# Main_Board_-_Single_v20_v4.net
KiCad netlist of a schematic drawn in EAGLE
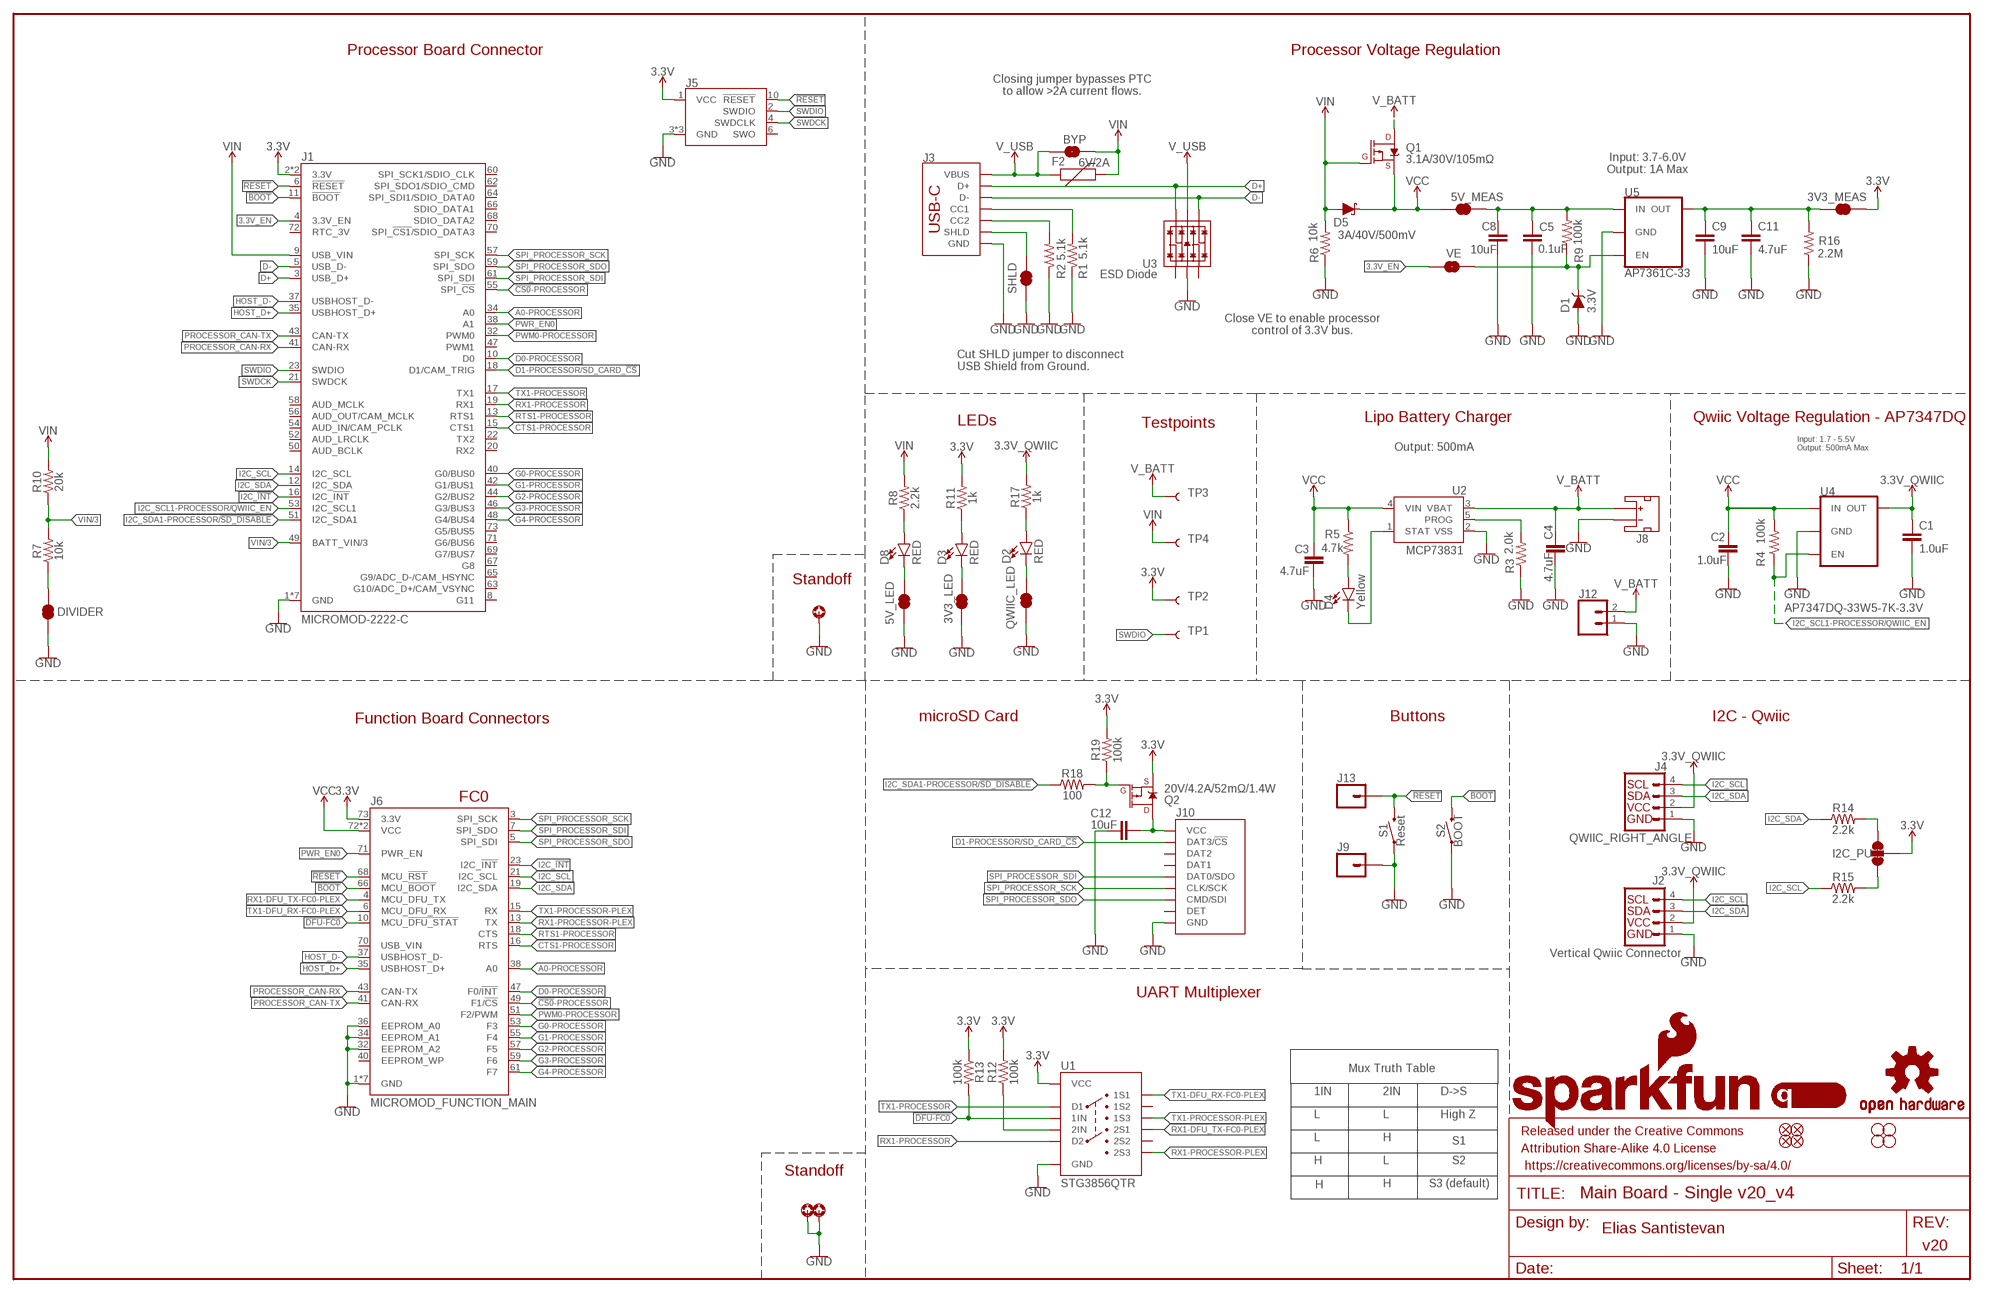
[diagram p0: schematic, sheet 1]

(export (version "E")
  (design (tool "Eeschema 10.0.6"))
  (components
    (comp (ref "3V3_LED")
      (value "JUMPER-SMT_2_NC_TRACE_SILK")
      (footprint "eagle-import:SMT-JUMPER_2_NC_TRACE_SILK")
      (libsource (lib "eagle-import") (part "JUMPER-SMT_2_NC_TRACE_SILK"))
    )
    (comp (ref "3V3_MEAS")
      (value "JUMPER-COMBO_2_NC_TRACE")
      (footprint "eagle-import:COMBO-JUMPER_2_NC_TRACE")
      (libsource (lib "eagle-import") (part "JUMPER-COMBO_2_NC_TRACE"))
    )
    (comp (ref "5V_LED")
      (value "JUMPER-SMT_2_NC_TRACE_SILK")
      (footprint "eagle-import:SMT-JUMPER_2_NC_TRACE_SILK")
      (libsource (lib "eagle-import") (part "JUMPER-SMT_2_NC_TRACE_SILK"))
    )
    (comp (ref "5V_MEAS")
      (value "JUMPER-COMBO_2_NC_TRACE")
      (footprint "eagle-import:COMBO-JUMPER_2_NC_TRACE")
      (libsource (lib "eagle-import") (part "JUMPER-COMBO_2_NC_TRACE"))
    )
    (comp (ref "BYP")
      (value "JUMPER-SMT_2_NO_SILK")
      (footprint "eagle-import:SMT-JUMPER_2_NO_SILK")
      (libsource (lib "eagle-import") (part "JUMPER-SMT_2_NO_SILK"))
    )
    (comp (ref "C1")
      (value "1.0uF")
      (footprint "eagle-import:0603")
      (libsource (lib "eagle-import") (part "1.0UF-0603-16V-10%"))
    )
    (comp (ref "C2")
      (value "1.0uF")
      (footprint "eagle-import:0603")
      (libsource (lib "eagle-import") (part "1.0UF-0603-16V-10%"))
    )
    (comp (ref "C3")
      (value "4.7uF")
      (footprint "eagle-import:0603")
      (libsource (lib "eagle-import") (part "4.7UF-0603-6.3V-(10%)"))
    )
    (comp (ref "C4")
      (value "4.7uF")
      (footprint "eagle-import:0603")
      (libsource (lib "eagle-import") (part "4.7UF-0603-35V-(20%)"))
    )
    (comp (ref "C5")
      (value "0.1uF")
      (footprint "eagle-import:0603")
      (libsource (lib "eagle-import") (part "0.1UF-0603-25V-(+80/-20%)"))
    )
    (comp (ref "C8")
      (value "10uF")
      (footprint "eagle-import:0805")
      (libsource (lib "eagle-import") (part "10UF-0805-10V-10%"))
    )
    (comp (ref "C9")
      (value "10uF")
      (footprint "eagle-import:0603")
      (libsource (lib "eagle-import") (part "10UF-0603-6.3V-20%"))
    )
    (comp (ref "C11")
      (value "4.7uF")
      (footprint "eagle-import:0603")
      (libsource (lib "eagle-import") (part "4.7UF-0603-6.3V-(10%)"))
    )
    (comp (ref "C12")
      (value "10uF")
      (footprint "eagle-import:0603")
      (libsource (lib "eagle-import") (part "10UF-0603-6.3V-20%"))
    )
    (comp (ref "D1")
      (value "3.3V")
      (footprint "eagle-import:SOD-323")
      (libsource (lib "eagle-import") (part "DIODE-ZENER-MM3Z3V3T1G"))
    )
    (comp (ref "D2")
      (value "RED")
      (footprint "eagle-import:LED-0603")
      (libsource (lib "eagle-import") (part "LED-RED0603"))
    )
    (comp (ref "D3")
      (value "RED")
      (footprint "eagle-import:LED-0603")
      (libsource (lib "eagle-import") (part "LED-RED0603"))
    )
    (comp (ref "D4")
      (value "Yellow")
      (footprint "eagle-import:LED-0603")
      (libsource (lib "eagle-import") (part "LED-YELLOW0603"))
    )
    (comp (ref "D5")
      (value "3A/40V/500mV")
      (footprint "eagle-import:SMA-DIODE")
      (libsource (lib "eagle-import") (part "DIODE-SCHOTTKY-B340A"))
    )
    (comp (ref "D8")
      (value "RED")
      (footprint "eagle-import:LED-0603")
      (libsource (lib "eagle-import") (part "LED-RED0603"))
    )
    (comp (ref "DIVIDER")
      (value "JUMPER-SMT_2_NC_TRACE_SILK")
      (footprint "eagle-import:SMT-JUMPER_2_NC_TRACE_SILK")
      (libsource (lib "eagle-import") (part "JUMPER-SMT_2_NC_TRACE_SILK"))
    )
    (comp (ref "F2")
      (value "6V/2A")
      (footprint "eagle-import:1210")
      (libsource (lib "eagle-import") (part "PPTC_6V2A"))
    )
    (comp (ref "FD1")
      (value "FIDUCIAL1X2")
      (footprint "eagle-import:FIDUCIAL-1X2")
      (libsource (lib "eagle-import") (part "FIDUCIAL1X2"))
    )
    (comp (ref "FD2")
      (value "FIDUCIAL1X2")
      (footprint "eagle-import:FIDUCIAL-1X2")
      (libsource (lib "eagle-import") (part "FIDUCIAL1X2"))
    )
    (comp (ref "FD3")
      (value "FIDUCIAL1X2")
      (footprint "eagle-import:FIDUCIAL-1X2")
      (libsource (lib "eagle-import") (part "FIDUCIAL1X2"))
    )
    (comp (ref "FD4")
      (value "FIDUCIAL1X2")
      (footprint "eagle-import:FIDUCIAL-1X2")
      (libsource (lib "eagle-import") (part "FIDUCIAL1X2"))
    )
    (comp (ref "FRAME1")
      (value "FRAME-LEDGER")
      (footprint "eagle-import:CREATIVE_COMMONS")
      (libsource (lib "eagle-import") (part "FRAME-LEDGER"))
    )
    (comp (ref "H2")
      (value "STAND-OFF-REFLOW-M2.5_2.5MM_TALL")
      (footprint "eagle-import:STAND-OFF-REFLOW-M2.5")
      (libsource (lib "eagle-import") (part "STAND-OFF-REFLOW-M2.5_2.5MM_TALL"))
    )
    (comp (ref "H4")
      (value "STAND-OFF-REFLOW-M2.5_2.5MM_TALL")
      (footprint "eagle-import:STAND-OFF-REFLOW-M2.5")
      (libsource (lib "eagle-import") (part "STAND-OFF-REFLOW-M2.5_2.5MM_TALL"))
    )
    (comp (ref "H8")
      (value "STAND-OFF-REFLOW-M2.5_2.5MM_TALL")
      (footprint "eagle-import:STAND-OFF-REFLOW-M2.5")
      (libsource (lib "eagle-import") (part "STAND-OFF-REFLOW-M2.5_2.5MM_TALL"))
    )
    (comp (ref "H14")
      (value "STAND-OFFTIGHT")
      (footprint "eagle-import:STAND-OFF-TIGHT")
      (libsource (lib "eagle-import") (part "STAND-OFFTIGHT"))
    )
    (comp (ref "H15")
      (value "STAND-OFFTIGHT")
      (footprint "eagle-import:STAND-OFF-TIGHT")
      (libsource (lib "eagle-import") (part "STAND-OFFTIGHT"))
    )
    (comp (ref "H16")
      (value "STAND-OFFTIGHT")
      (footprint "eagle-import:STAND-OFF-TIGHT")
      (libsource (lib "eagle-import") (part "STAND-OFFTIGHT"))
    )
    (comp (ref "H17")
      (value "STAND-OFFTIGHT")
      (footprint "eagle-import:STAND-OFF-TIGHT")
      (libsource (lib "eagle-import") (part "STAND-OFFTIGHT"))
    )
    (comp (ref "I2C_PU")
      (value "JUMPER-SMT_3_2-NC_TRACE_SILK")
      (footprint "eagle-import:SMT-JUMPER_3_2-NC_TRACE_SILK")
      (libsource (lib "eagle-import") (part "JUMPER-SMT_3_2-NC_TRACE_SILK"))
    )
    (comp (ref "J1")
      (value "MICROMOD-2222-C")
      (footprint "eagle-import:M.2-CONNECTOR-E")
      (libsource (lib "eagle-import") (part "MICROMOD-2222-C"))
    )
    (comp (ref "J2")
      (value "Vertical Qwiic Connector")
      (footprint "eagle-import:JST04_1MM_VERT")
      (libsource (lib "eagle-import") (part "QWIIC_CONNECTOR"))
    )
    (comp (ref "J3")
      (value "USB_C_2-LAYER_PADS")
      (footprint "eagle-import:USB-C-16P-2LAYER-PADS")
      (libsource (lib "eagle-import") (part "USB_C_2-LAYER_PADS"))
    )
    (comp (ref "J4")
      (value "QWIIC_RIGHT_ANGLE")
      (footprint "eagle-import:JST04_1MM_RA")
      (libsource (lib "eagle-import") (part "QWIIC_CONNECTORJS-1MM"))
    )
    (comp (ref "J5")
      (value "CORTEX_JTAG_DEBUG_MINIMUM_PTH")
      (footprint "eagle-import:2X5-PTH-1.27MM")
      (libsource (lib "eagle-import") (part "CORTEX_JTAG_DEBUG_MINIMUM_PTH"))
    )
    (comp (ref "J6")
      (value "MICROMOD_FUNCTION_MAIN")
      (footprint "eagle-import:M.2-CONNECTOR-E-FUNCTION-STANDARD")
      (libsource (lib "eagle-import") (part "MICROMOD_FUNCTION_MAIN"))
    )
    (comp (ref "J8")
      (value "JST_2MM_MALE")
      (footprint "eagle-import:JST-2-SMD")
      (libsource (lib "eagle-import") (part "JST_2MM_MALE"))
    )
    (comp (ref "J9")
      (value "CONN_01PTH_NO_SILK_YES_STOP")
      (footprint "eagle-import:1X01_NO_SILK")
      (libsource (lib "eagle-import") (part "CONN_01PTH_NO_SILK_YES_STOP"))
    )
    (comp (ref "J10")
      (value "MICRO-SD-PUSH-PUSH-EXT-PIN")
      (footprint "eagle-import:MICROSD-EXTERNALPIN")
      (libsource (lib "eagle-import") (part "MICRO-SD-PUSH-PUSH-EXT-PIN"))
    )
    (comp (ref "J12")
      (value "CONN_021X02_NO_SILK")
      (footprint "eagle-import:1X02_NO_SILK")
      (libsource (lib "eagle-import") (part "CONN_021X02_NO_SILK"))
    )
    (comp (ref "J13")
      (value "CONN_01PTH_NO_SILK_YES_STOP")
      (footprint "eagle-import:1X01_NO_SILK")
      (libsource (lib "eagle-import") (part "CONN_01PTH_NO_SILK_YES_STOP"))
    )
    (comp (ref "LOGO1")
      (value "QWIIC_LOGO_8MM")
      (footprint "eagle-import:QWIIC_8MM")
      (libsource (lib "eagle-import") (part "QWIIC_LOGO_8MM"))
    )
    (comp (ref "LOGO2")
      (value "SFE_LOGO_NAME_FLAME.3_INCH")
      (footprint "eagle-import:SFE_LOGO_NAME_FLAME_.3")
      (libsource (lib "eagle-import") (part "SFE_LOGO_NAME_FLAME.3_INCH"))
    )
    (comp (ref "LOGO3")
      (value "OSHW-LOGOL")
      (footprint "eagle-import:OSHW-LOGO-L")
      (libsource (lib "eagle-import") (part "OSHW-LOGOL"))
    )
    (comp (ref "Q1")
      (value "3.1A/30V/105mΩ")
      (footprint "eagle-import:SOT23-3")
      (libsource (lib "eagle-import") (part "MOSFET_PCH-DMG2307L"))
    )
    (comp (ref "Q2")
      (value "20V/4.2A/52mΩ/1.4W")
      (footprint "eagle-import:SOT23-3")
      (libsource (lib "eagle-import") (part "MOSFET_PCH-DMG2305UX-7"))
    )
    (comp (ref "QWIIC_LED")
      (value "JUMPER-SMT_2_NC_TRACE_SILK")
      (footprint "eagle-import:SMT-JUMPER_2_NC_TRACE_SILK")
      (libsource (lib "eagle-import") (part "JUMPER-SMT_2_NC_TRACE_SILK"))
    )
    (comp (ref "R1")
      (value "5.1k")
      (footprint "eagle-import:0603")
      (libsource (lib "eagle-import") (part "5.1KOHM5.1KOHM-0603-1/10W-1%"))
    )
    (comp (ref "R2")
      (value "5.1k")
      (footprint "eagle-import:0603")
      (libsource (lib "eagle-import") (part "5.1KOHM5.1KOHM-0603-1/10W-1%"))
    )
    (comp (ref "R3")
      (value "2.0k")
      (footprint "eagle-import:0603")
      (libsource (lib "eagle-import") (part "2.0KOHM-0603-1/10W-5%"))
    )
    (comp (ref "R4")
      (value "100k")
      (footprint "eagle-import:0603")
      (libsource (lib "eagle-import") (part "100KOHM-0603-1/10W-1%"))
    )
    (comp (ref "R5")
      (value "4.7k")
      (footprint "eagle-import:0603")
      (libsource (lib "eagle-import") (part "4.7KOHM-0603-1/10W-1%"))
    )
    (comp (ref "R6")
      (value "10k")
      (footprint "eagle-import:0603")
      (libsource (lib "eagle-import") (part "10KOHM-0603-1/10W-1%"))
    )
    (comp (ref "R7")
      (value "10k")
      (footprint "eagle-import:0603")
      (libsource (lib "eagle-import") (part "10KOHM-0603-1/10W-1%"))
    )
    (comp (ref "R8")
      (value "2.2k")
      (footprint "eagle-import:0603")
      (libsource (lib "eagle-import") (part "2.2KOHM-0603-1/10W-1%"))
    )
    (comp (ref "R9")
      (value "100k")
      (footprint "eagle-import:0603")
      (libsource (lib "eagle-import") (part "100KOHM-0603-1/10W-1%"))
    )
    (comp (ref "R10")
      (value "20k")
      (footprint "eagle-import:0603")
      (libsource (lib "eagle-import") (part "20KOHM-0603-1/10W-1%"))
    )
    (comp (ref "R11")
      (value "1k")
      (footprint "eagle-import:0603")
      (libsource (lib "eagle-import") (part "1KOHM-0603-1/10W-1%"))
    )
    (comp (ref "R12")
      (value "100k")
      (footprint "eagle-import:0603")
      (libsource (lib "eagle-import") (part "100KOHM-0603-1/10W-1%"))
    )
    (comp (ref "R13")
      (value "100k")
      (footprint "eagle-import:0603")
      (libsource (lib "eagle-import") (part "100KOHM-0603-1/10W-1%"))
    )
    (comp (ref "R14")
      (value "2.2k")
      (footprint "eagle-import:0603")
      (libsource (lib "eagle-import") (part "2.2KOHM-0603-1/10W-1%"))
    )
    (comp (ref "R15")
      (value "2.2k")
      (footprint "eagle-import:0603")
      (libsource (lib "eagle-import") (part "2.2KOHM-0603-1/10W-1%"))
    )
    (comp (ref "R16")
      (value "2.2M")
      (footprint "eagle-import:0603")
      (libsource (lib "eagle-import") (part "2.2MOHMS-0603-1/10W-1%"))
    )
    (comp (ref "R17")
      (value "1k")
      (footprint "eagle-import:0603")
      (libsource (lib "eagle-import") (part "1KOHM-0603-1/10W-1%"))
    )
    (comp (ref "R18")
      (value "100")
      (footprint "eagle-import:0603")
      (libsource (lib "eagle-import") (part "100OHM-0603-1/10W-1%"))
    )
    (comp (ref "R19")
      (value "100k")
      (footprint "eagle-import:0603")
      (libsource (lib "eagle-import") (part "100KOHM-0603-1/10W-1%"))
    )
    (comp (ref "S1")
      (value "Reset")
      (footprint "eagle-import:TACTILE_SWITCH_SMD_5.2MM")
      (libsource (lib "eagle-import") (part "MOMENTARY-SWITCH-SPST-SMD-5.2-TALL-REDUNDANT"))
    )
    (comp (ref "S2")
      (value "BOOT")
      (footprint "eagle-import:TACTILE_SWITCH_SMD_5.2MM")
      (libsource (lib "eagle-import") (part "MOMENTARY-SWITCH-SPST-SMD-5.2-TALL-REDUNDANT"))
    )
    (comp (ref "SHLD")
      (value "JUMPER-SMT_2_NC_TRACE_SILK")
      (footprint "eagle-import:SMT-JUMPER_2_NC_TRACE_SILK")
      (libsource (lib "eagle-import") (part "JUMPER-SMT_2_NC_TRACE_SILK"))
    )
    (comp (ref "TP1")
      (value "TEST-POINT3X5")
      (footprint "eagle-import:PAD.03X.05")
      (libsource (lib "eagle-import") (part "TEST-POINT3X5"))
    )
    (comp (ref "TP2")
      (value "TEST-POINT3X5")
      (footprint "eagle-import:PAD.03X.05")
      (libsource (lib "eagle-import") (part "TEST-POINT3X5"))
    )
    (comp (ref "TP3")
      (value "TEST-POINT3X5")
      (footprint "eagle-import:PAD.03X.05")
      (libsource (lib "eagle-import") (part "TEST-POINT3X5"))
    )
    (comp (ref "TP4")
      (value "TEST-POINT3X5")
      (footprint "eagle-import:PAD.03X.05")
      (libsource (lib "eagle-import") (part "TEST-POINT3X5"))
    )
    (comp (ref "U1")
      (value "STG3856QTR")
      (footprint "eagle-import:STG3856")
      (libsource (lib "eagle-import") (part "STG3856QTR"))
    )
    (comp (ref "U2")
      (value "MCP73831")
      (footprint "eagle-import:SOT23-5")
      (libsource (lib "eagle-import") (part "MCP73831"))
    )
    (comp (ref "U3")
      (value "ESD Diode")
      (footprint "eagle-import:SOT-23-6")
      (libsource (lib "eagle-import") (part "TVS_DIODE_ARRAYSMD"))
    )
    (comp (ref "U4")
      (value "AP7347DQ-33W5-7K-3.3V")
      (footprint "eagle-import:SOT25")
      (libsource (lib "eagle-import") (part "AP7347DQ-33W5-7K-3.3V"))
    )
    (comp (ref "U5")
      (value "AP7361C-33")
      (footprint "eagle-import:UDFN-8")
      (libsource (lib "eagle-import") (part "AP7361C-33FGEUDFN-8"))
    )
    (comp (ref "VE")
      (value "JUMPER-SMT_2_NO_SILK")
      (footprint "eagle-import:SMT-JUMPER_2_NO_SILK")
      (libsource (lib "eagle-import") (part "JUMPER-SMT_2_NO_SILK"))
    )
  )
  (nets
    (net (code "1") (name "/D1-PROCESSOR{slash}SD_CARD_~{CS}") (class "Default")
      (node (ref "J1") (pin "18") (pinfunction "D1/CAM_TRIG_18") (pintype "bidirectional"))
      (node (ref "J10") (pin "2") (pinfunction "DAT3/~{CS}_2") (pintype "bidirectional"))
    )
    (net (code "2") (name "/I2C_SDA1-PROCESSOR{slash}~{SD_DISABLE}") (class "Default")
      (node (ref "J1") (pin "51") (pinfunction "I2C_SDA1_51") (pintype "bidirectional"))
      (node (ref "R18") (pin "1") (pinfunction "1_1") (pintype "passive"))
    )
    (net (code "3") (name "/I2C_~{INT}") (class "Default")
      (node (ref "J1") (pin "16") (pinfunction "I2C_~{INT}_16") (pintype "bidirectional"))
      (node (ref "J6") (pin "23") (pinfunction "I2C_~{INT}_23") (pintype "bidirectional"))
    )
    (net (code "4") (name "/~{BOOT}") (class "Default")
      (node (ref "J1") (pin "11") (pinfunction "~{BOOT}_11") (pintype "bidirectional"))
      (node (ref "J6") (pin "66") (pinfunction "MCU_~{BOOT}_66") (pintype "bidirectional"))
      (node (ref "S2") (pin "3") (pinfunction "2_3") (pintype "passive"))
      (node (ref "S2") (pin "4") (pinfunction "2_4") (pintype "passive"))
    )
    (net (code "5") (name "/~{CS0}-PROCESSOR") (class "Default")
      (node (ref "J1") (pin "55") (pinfunction "SPI_~{CS}_55") (pintype "bidirectional"))
      (node (ref "J6") (pin "49") (pinfunction "F1/~{CS}_49") (pintype "bidirectional"))
    )
    (net (code "6") (name "/~{DFU-FC0}") (class "Default")
      (node (ref "J6") (pin "10") (pinfunction "MCU_~{DFU_STAT}_10") (pintype "bidirectional"))
      (node (ref "R13") (pin "2") (pinfunction "2_2") (pintype "passive"))
      (node (ref "U1") (pin "P12") (pinfunction "1IN_P12") (pintype "bidirectional"))
    )
    (net (code "7") (name "/~{RESET}") (class "Default")
      (node (ref "J1") (pin "6") (pinfunction "~{RESET}_6") (pintype "bidirectional"))
      (node (ref "J13") (pin "1") (pinfunction "1_1") (pintype "passive"))
      (node (ref "J5") (pin "10") (pinfunction "~{RESET}_10") (pintype "bidirectional"))
      (node (ref "J6") (pin "68") (pinfunction "MCU_~{RST}_68") (pintype "bidirectional"))
      (node (ref "S1") (pin "3") (pinfunction "2_3") (pintype "passive"))
      (node (ref "S1") (pin "4") (pinfunction "2_4") (pintype "passive"))
    )
    (net (code "8") (name "3.3V") (class "Default")
      (node (ref "3V3_MEAS") (pin "2") (pinfunction "2_2") (pintype "passive"))
      (node (ref "3V3_MEAS") (pin "4") (pinfunction "2_4") (pintype "passive"))
      (node (ref "I2C_PU") (pin "2") (pinfunction "2_2") (pintype "passive"))
      (node (ref "J1") (pin "2") (pinfunction "3.3V_2") (pintype "bidirectional"))
      (node (ref "J1") (pin "74") (pinfunction "3.3V_74") (pintype "bidirectional"))
      (node (ref "J5") (pin "1") (pinfunction "VCC_1") (pintype "bidirectional"))
      (node (ref "J6") (pin "73") (pinfunction "3.3V_73") (pintype "bidirectional"))
      (node (ref "Q2") (pin "2") (pinfunction "S_2") (pintype "bidirectional"))
      (node (ref "R11") (pin "2") (pinfunction "2_2") (pintype "passive"))
      (node (ref "R12") (pin "2") (pinfunction "2_2") (pintype "passive"))
      (node (ref "R13") (pin "1") (pinfunction "1_1") (pintype "passive"))
      (node (ref "R19") (pin "2") (pinfunction "2_2") (pintype "passive"))
      (node (ref "TP2") (pin "1") (pinfunction "1_1") (pintype "bidirectional"))
      (node (ref "U1") (pin "P11") (pinfunction "VCC_P11") (pintype "power_in"))
    )
    (net (code "9") (name "3.3V_EN") (class "Default")
      (node (ref "J1") (pin "4") (pinfunction "3.3V_EN_4") (pintype "bidirectional"))
      (node (ref "VE") (pin "1") (pinfunction "1_1") (pintype "passive"))
    )
    (net (code "10") (name "3.3V_QWIIC") (class "Default")
      (node (ref "C1") (pin "1") (pinfunction "1_1") (pintype "passive"))
      (node (ref "J2") (pin "2") (pinfunction "2_2") (pintype "power_in"))
      (node (ref "J4") (pin "2") (pinfunction "2_2") (pintype "power_in"))
      (node (ref "R17") (pin "2") (pinfunction "2_2") (pintype "passive"))
      (node (ref "U4") (pin "5") (pinfunction "OUT_5") (pintype "passive"))
    )
    (net (code "11") (name "A0-PROCESSOR") (class "Default")
      (node (ref "J1") (pin "34") (pinfunction "A0_34") (pintype "bidirectional"))
      (node (ref "J6") (pin "38") (pinfunction "A0_38") (pintype "bidirectional"))
    )
    (net (code "12") (name "CTS1-PROCESSOR") (class "Default")
      (node (ref "J1") (pin "15") (pinfunction "CTS1_15") (pintype "bidirectional"))
      (node (ref "J6") (pin "16") (pinfunction "RTS_16") (pintype "bidirectional"))
    )
    (net (code "13") (name "D+") (class "Default")
      (node (ref "J1") (pin "3") (pinfunction "USB_D+_3") (pintype "bidirectional"))
      (node (ref "J3") (pin "A6") (pinfunction "D+_A6") (pintype "bidirectional"))
      (node (ref "J3") (pin "B6") (pinfunction "D+_B6") (pintype "bidirectional"))
      (node (ref "U3") (pin "6") (pinfunction "IO4_6") (pintype "bidirectional"))
    )
    (net (code "14") (name "D-") (class "Default")
      (node (ref "J1") (pin "5") (pinfunction "USB_D-_5") (pintype "bidirectional"))
      (node (ref "J3") (pin "A7") (pinfunction "D-_A7") (pintype "bidirectional"))
      (node (ref "J3") (pin "B7") (pinfunction "D-_B7") (pintype "bidirectional"))
      (node (ref "U3") (pin "4") (pinfunction "IO3_4") (pintype "bidirectional"))
    )
    (net (code "15") (name "D0-PROCESSOR") (class "Default")
      (node (ref "J1") (pin "10") (pinfunction "D0_10") (pintype "bidirectional"))
      (node (ref "J6") (pin "47") (pinfunction "F0/~{INT}_47") (pintype "bidirectional"))
    )
    (net (code "16") (name "G0-PROCESSOR") (class "Default")
      (node (ref "J1") (pin "40") (pinfunction "G0/BUS0_40") (pintype "bidirectional"))
      (node (ref "J6") (pin "53") (pinfunction "F3_53") (pintype "bidirectional"))
    )
    (net (code "17") (name "G1-PROCESSOR") (class "Default")
      (node (ref "J1") (pin "42") (pinfunction "G1/BUS1_42") (pintype "bidirectional"))
      (node (ref "J6") (pin "55") (pinfunction "F4_55") (pintype "bidirectional"))
    )
    (net (code "18") (name "G2-PROCESSOR") (class "Default")
      (node (ref "J1") (pin "44") (pinfunction "G2/BUS2_44") (pintype "bidirectional"))
      (node (ref "J6") (pin "57") (pinfunction "F5_57") (pintype "bidirectional"))
    )
    (net (code "19") (name "G3-PROCESSOR") (class "Default")
      (node (ref "J1") (pin "46") (pinfunction "G3/BUS3_46") (pintype "bidirectional"))
      (node (ref "J6") (pin "59") (pinfunction "F6_59") (pintype "bidirectional"))
    )
    (net (code "20") (name "G4-PROCESSOR") (class "Default")
      (node (ref "J1") (pin "48") (pinfunction "G4/BUS4_48") (pintype "bidirectional"))
      (node (ref "J6") (pin "61") (pinfunction "F7_61") (pintype "bidirectional"))
    )
    (net (code "21") (name "GND") (class "Default")
      (node (ref "3V3_LED") (pin "1") (pinfunction "1_1") (pintype "passive"))
      (node (ref "5V_LED") (pin "1") (pinfunction "1_1") (pintype "passive"))
      (node (ref "C1") (pin "2") (pinfunction "2_2") (pintype "passive"))
      (node (ref "C11") (pin "2") (pinfunction "2_2") (pintype "passive"))
      (node (ref "C12") (pin "2") (pinfunction "2_2") (pintype "passive"))
      (node (ref "C2") (pin "2") (pinfunction "2_2") (pintype "passive"))
      (node (ref "C3") (pin "2") (pinfunction "2_2") (pintype "passive"))
      (node (ref "C4") (pin "2") (pinfunction "2_2") (pintype "passive"))
      (node (ref "C5") (pin "2") (pinfunction "2_2") (pintype "passive"))
      (node (ref "C8") (pin "2") (pinfunction "2_2") (pintype "passive"))
      (node (ref "C9") (pin "2") (pinfunction "2_2") (pintype "passive"))
      (node (ref "D1") (pin "A") (pinfunction "A_A") (pintype "passive"))
      (node (ref "DIVIDER") (pin "1") (pinfunction "1_1") (pintype "passive"))
      (node (ref "H2") (pin "1") (pinfunction "1_1") (pintype "bidirectional"))
      (node (ref "H4") (pin "1") (pinfunction "1_1") (pintype "bidirectional"))
      (node (ref "H8") (pin "1") (pinfunction "1_1") (pintype "bidirectional"))
      (node (ref "J1") (pin "1") (pinfunction "GND_1") (pintype "bidirectional"))
      (node (ref "J1") (pin "33") (pinfunction "GND_33") (pintype "bidirectional"))
      (node (ref "J1") (pin "36") (pinfunction "GND_36") (pintype "bidirectional"))
      (node (ref "J1") (pin "39") (pinfunction "GND_39") (pintype "bidirectional"))
      (node (ref "J1") (pin "45") (pinfunction "GND_45") (pintype "bidirectional"))
      (node (ref "J1") (pin "7") (pinfunction "GND_7") (pintype "bidirectional"))
      (node (ref "J1") (pin "75") (pinfunction "GND_75") (pintype "bidirectional"))
      (node (ref "J10") (pin "10") (pinfunction "GND_10") (pintype "bidirectional"))
      (node (ref "J10") (pin "11") (pinfunction "GND_11") (pintype "bidirectional"))
      (node (ref "J10") (pin "12") (pinfunction "GND_12") (pintype "bidirectional"))
      (node (ref "J10") (pin "13") (pinfunction "GND_13") (pintype "bidirectional"))
      (node (ref "J10") (pin "6") (pinfunction "GND_6") (pintype "bidirectional"))
      (node (ref "J12") (pin "1") (pinfunction "1_1") (pintype "passive"))
      (node (ref "J2") (pin "1") (pinfunction "1_1") (pintype "power_in"))
      (node (ref "J3") (pin "GND") (pinfunction "GND_GND") (pintype "bidirectional"))
      (node (ref "J3") (pin "GND2") (pinfunction "GND_GND2") (pintype "bidirectional"))
      (node (ref "J4") (pin "1") (pinfunction "1_1") (pintype "power_in"))
      (node (ref "J5") (pin "3") (pinfunction "GND_3") (pintype "bidirectional"))
      (node (ref "J5") (pin "5") (pinfunction "GND_5") (pintype "bidirectional"))
      (node (ref "J5") (pin "9") (pinfunction "GND_9") (pintype "bidirectional"))
      (node (ref "J6") (pin "1") (pinfunction "GND_1") (pintype "bidirectional"))
      (node (ref "J6") (pin "2") (pinfunction "GND_2") (pintype "bidirectional"))
      (node (ref "J6") (pin "32") (pinfunction "EEPROM_A2_32") (pintype "bidirectional"))
      (node (ref "J6") (pin "33") (pinfunction "GND_33") (pintype "bidirectional"))
      (node (ref "J6") (pin "34") (pinfunction "EEPROM_A1_34") (pintype "bidirectional"))
      (node (ref "J6") (pin "36") (pinfunction "EEPROM_A0_36") (pintype "bidirectional"))
      (node (ref "J6") (pin "39") (pinfunction "GND_39") (pintype "bidirectional"))
      (node (ref "J6") (pin "45") (pinfunction "GND_45") (pintype "bidirectional"))
      (node (ref "J6") (pin "75") (pinfunction "GND_75") (pintype "bidirectional"))
      (node (ref "J6") (pin "8") (pinfunction "GND_8") (pintype "bidirectional"))
      (node (ref "J8") (pin "1") (pinfunction "-_1") (pintype "bidirectional"))
      (node (ref "J9") (pin "1") (pinfunction "1_1") (pintype "passive"))
      (node (ref "QWIIC_LED") (pin "1") (pinfunction "1_1") (pintype "passive"))
      (node (ref "R1") (pin "1") (pinfunction "1_1") (pintype "passive"))
      (node (ref "R16") (pin "1") (pinfunction "1_1") (pintype "passive"))
      (node (ref "R2") (pin "1") (pinfunction "1_1") (pintype "passive"))
      (node (ref "R3") (pin "1") (pinfunction "1_1") (pintype "passive"))
      (node (ref "R6") (pin "1") (pinfunction "1_1") (pintype "passive"))
      (node (ref "S1") (pin "1") (pinfunction "1_1") (pintype "passive"))
      (node (ref "S1") (pin "2") (pinfunction "1_2") (pintype "passive"))
      (node (ref "S2") (pin "1") (pinfunction "1_1") (pintype "passive"))
      (node (ref "S2") (pin "2") (pinfunction "1_2") (pintype "passive"))
      (node (ref "SHLD") (pin "1") (pinfunction "1_1") (pintype "passive"))
      (node (ref "U1") (pin "P5") (pinfunction "GND_P5") (pintype "power_in"))
      (node (ref "U2") (pin "2") (pinfunction "VSS_2") (pintype "power_in"))
      (node (ref "U3") (pin "2") (pinfunction "VSS_2") (pintype "bidirectional"))
      (node (ref "U4") (pin "2") (pinfunction "GND_2") (pintype "input"))
      (node (ref "U5") (pin "4") (pinfunction "GND_4") (pintype "input"))
      (node (ref "U5") (pin "EP") (pinfunction "GND_EP") (pintype "input"))
    )
    (net (code "22") (name "HOST_D+") (class "Default")
      (node (ref "J1") (pin "35") (pinfunction "USBHOST_D+_35") (pintype "bidirectional"))
      (node (ref "J6") (pin "35") (pinfunction "USBHOST_D+_35") (pintype "bidirectional"))
    )
    (net (code "23") (name "HOST_D-") (class "Default")
      (node (ref "J1") (pin "37") (pinfunction "USBHOST_D-_37") (pintype "bidirectional"))
      (node (ref "J6") (pin "37") (pinfunction "USBHOST_D-_37") (pintype "bidirectional"))
    )
    (net (code "24") (name "I2C_SCL") (class "Default")
      (node (ref "J1") (pin "14") (pinfunction "I2C_SCL_14") (pintype "bidirectional"))
      (node (ref "J2") (pin "4") (pinfunction "4_4") (pintype "passive"))
      (node (ref "J4") (pin "4") (pinfunction "4_4") (pintype "passive"))
      (node (ref "J6") (pin "21") (pinfunction "I2C_SCL_21") (pintype "bidirectional"))
      (node (ref "R15") (pin "1") (pinfunction "1_1") (pintype "passive"))
    )
    (net (code "25") (name "I2C_SCL1-PROCESSOR{slash}QWIIC_EN") (class "Default")
      (node (ref "J1") (pin "53") (pinfunction "I2C_SCL1_53") (pintype "bidirectional"))
      (node (ref "R4") (pin "1") (pinfunction "1_1") (pintype "passive"))
      (node (ref "U4") (pin "3") (pinfunction "EN_3") (pintype "input"))
    )
    (net (code "26") (name "I2C_SDA") (class "Default")
      (node (ref "J1") (pin "12") (pinfunction "I2C_SDA_12") (pintype "bidirectional"))
      (node (ref "J2") (pin "3") (pinfunction "3_3") (pintype "passive"))
      (node (ref "J4") (pin "3") (pinfunction "3_3") (pintype "passive"))
      (node (ref "J6") (pin "19") (pinfunction "I2C_SDA_19") (pintype "bidirectional"))
      (node (ref "R14") (pin "1") (pinfunction "1_1") (pintype "passive"))
    )
    (net (code "27") (name "Net-(3V3_LED-Pad2)") (class "Default")
      (node (ref "3V3_LED") (pin "2") (pinfunction "2_2") (pintype "passive"))
      (node (ref "D3") (pin "C") (pinfunction "C_C") (pintype "passive"))
    )
    (net (code "28") (name "Net-(5V_LED-Pad2)") (class "Default")
      (node (ref "5V_LED") (pin "2") (pinfunction "2_2") (pintype "passive"))
      (node (ref "D8") (pin "C") (pinfunction "C_C") (pintype "passive"))
    )
    (net (code "29") (name "Net-(D2-PadA)") (class "Default")
      (node (ref "D2") (pin "A") (pinfunction "A_A") (pintype "passive"))
      (node (ref "R17") (pin "1") (pinfunction "1_1") (pintype "passive"))
    )
    (net (code "30") (name "Net-(D2-PadC)") (class "Default")
      (node (ref "D2") (pin "C") (pinfunction "C_C") (pintype "passive"))
      (node (ref "QWIIC_LED") (pin "2") (pinfunction "2_2") (pintype "passive"))
    )
    (net (code "31") (name "Net-(D3-PadA)") (class "Default")
      (node (ref "D3") (pin "A") (pinfunction "A_A") (pintype "passive"))
      (node (ref "R11") (pin "1") (pinfunction "1_1") (pintype "passive"))
    )
    (net (code "32") (name "Net-(D4-PadA)") (class "Default")
      (node (ref "D4") (pin "A") (pinfunction "A_A") (pintype "passive"))
      (node (ref "R5") (pin "2") (pinfunction "2_2") (pintype "passive"))
    )
    (net (code "33") (name "Net-(D8-PadA)") (class "Default")
      (node (ref "D8") (pin "A") (pinfunction "A_A") (pintype "passive"))
      (node (ref "R8") (pin "1") (pinfunction "1_1") (pintype "passive"))
    )
    (net (code "34") (name "Net-(DIVIDER-Pad2)") (class "Default")
      (node (ref "DIVIDER") (pin "2") (pinfunction "2_2") (pintype "passive"))
      (node (ref "R7") (pin "1") (pinfunction "1_1") (pintype "passive"))
    )
    (net (code "35") (name "Net-(I2C_PU-Pad1)") (class "Default")
      (node (ref "I2C_PU") (pin "1") (pinfunction "1_1") (pintype "passive"))
      (node (ref "R15") (pin "2") (pinfunction "2_2") (pintype "passive"))
    )
    (net (code "36") (name "Net-(I2C_PU-Pad3)") (class "Default")
      (node (ref "I2C_PU") (pin "3") (pinfunction "3_3") (pintype "passive"))
      (node (ref "R14") (pin "2") (pinfunction "2_2") (pintype "passive"))
    )
    (net (code "37") (name "Net-(J3-CC1)") (class "Default")
      (node (ref "J3") (pin "A5") (pinfunction "CC1_A5") (pintype "bidirectional"))
      (node (ref "R1") (pin "2") (pinfunction "2_2") (pintype "passive"))
    )
    (net (code "38") (name "Net-(J3-CC2)") (class "Default")
      (node (ref "J3") (pin "B5") (pinfunction "CC2_B5") (pintype "bidirectional"))
      (node (ref "R2") (pin "2") (pinfunction "2_2") (pintype "passive"))
    )
    (net (code "39") (name "Net-(J3-SHLD-PadSHLD1)") (class "Default")
      (node (ref "J3") (pin "SHLD1") (pinfunction "SHLD_SHLD1") (pintype "bidirectional"))
      (node (ref "J3") (pin "SHLD2") (pinfunction "SHLD_SHLD2") (pintype "bidirectional"))
      (node (ref "J3") (pin "SHLD3") (pinfunction "SHLD_SHLD3") (pintype "bidirectional"))
      (node (ref "J3") (pin "SHLD4") (pinfunction "SHLD_SHLD4") (pintype "bidirectional"))
      (node (ref "SHLD") (pin "2") (pinfunction "2_2") (pintype "passive"))
    )
    (net (code "40") (name "Net-(J10-VCC)") (class "Default")
      (node (ref "C12") (pin "1") (pinfunction "1_1") (pintype "passive"))
      (node (ref "J10") (pin "4") (pinfunction "VCC_4") (pintype "bidirectional"))
      (node (ref "Q2") (pin "3") (pinfunction "D_3") (pintype "bidirectional"))
    )
    (net (code "41") (name "Net-(Q2-G)") (class "Default")
      (node (ref "Q2") (pin "1") (pinfunction "G_1") (pintype "bidirectional"))
      (node (ref "R18") (pin "2") (pinfunction "2_2") (pintype "passive"))
      (node (ref "R19") (pin "1") (pinfunction "1_1") (pintype "passive"))
    )
    (net (code "42") (name "Net-(U1-2IN)") (class "Default")
      (node (ref "R12") (pin "1") (pinfunction "1_1") (pintype "passive"))
      (node (ref "U1") (pin "P10") (pinfunction "2IN_P10") (pintype "bidirectional"))
    )
    (net (code "43") (name "Net-(U2-PROG)") (class "Default")
      (node (ref "R3") (pin "2") (pinfunction "2_2") (pintype "passive"))
      (node (ref "U2") (pin "5") (pinfunction "PROG_5") (pintype "input"))
    )
    (net (code "44") (name "Net-(U2-STAT)") (class "Default")
      (node (ref "D4") (pin "C") (pinfunction "C_C") (pintype "passive"))
      (node (ref "U2") (pin "1") (pinfunction "STAT_1") (pintype "output"))
    )
    (net (code "45") (name "Net-(U5-EN)") (class "Default")
      (node (ref "D1") (pin "C") (pinfunction "C_C") (pintype "passive"))
      (node (ref "R9") (pin "1") (pinfunction "1_1") (pintype "passive"))
      (node (ref "U5") (pin "5") (pinfunction "EN_5") (pintype "bidirectional"))
      (node (ref "VE") (pin "2") (pinfunction "2_2") (pintype "passive"))
    )
    (net (code "46") (name "Net-(U5-IN)") (class "Default")
      (node (ref "5V_MEAS") (pin "2") (pinfunction "2_2") (pintype "passive"))
      (node (ref "5V_MEAS") (pin "4") (pinfunction "2_4") (pintype "passive"))
      (node (ref "C5") (pin "1") (pinfunction "1_1") (pintype "passive"))
      (node (ref "C8") (pin "1") (pinfunction "1_1") (pintype "passive"))
      (node (ref "R9") (pin "2") (pinfunction "2_2") (pintype "passive"))
      (node (ref "U5") (pin "8") (pinfunction "IN_8") (pintype "input"))
    )
    (net (code "47") (name "Net-(U5-OUT)") (class "Default")
      (node (ref "3V3_MEAS") (pin "1") (pinfunction "1_1") (pintype "passive"))
      (node (ref "3V3_MEAS") (pin "3") (pinfunction "1_3") (pintype "passive"))
      (node (ref "C11") (pin "1") (pinfunction "1_1") (pintype "passive"))
      (node (ref "C9") (pin "1") (pinfunction "1_1") (pintype "passive"))
      (node (ref "R16") (pin "2") (pinfunction "2_2") (pintype "passive"))
      (node (ref "U5") (pin "1") (pinfunction "OUT_1") (pintype "output"))
    )
    (net (code "48") (name "PROCESSOR_CAN-RX") (class "Default")
      (node (ref "J1") (pin "41") (pinfunction "CAN-RX_41") (pintype "bidirectional"))
      (node (ref "J6") (pin "43") (pinfunction "CAN-TX_43") (pintype "bidirectional"))
    )
    (net (code "49") (name "PROCESSOR_CAN-TX") (class "Default")
      (node (ref "J1") (pin "43") (pinfunction "CAN-TX_43") (pintype "bidirectional"))
      (node (ref "J6") (pin "41") (pinfunction "CAN-RX_41") (pintype "bidirectional"))
    )
    (net (code "50") (name "PWM0-PROCESSOR") (class "Default")
      (node (ref "J1") (pin "32") (pinfunction "PWM0_32") (pintype "bidirectional"))
      (node (ref "J6") (pin "51") (pinfunction "F2/PWM_51") (pintype "bidirectional"))
    )
    (net (code "51") (name "PWR_EN0") (class "Default")
      (node (ref "J1") (pin "38") (pinfunction "A1_38") (pintype "bidirectional"))
      (node (ref "J6") (pin "71") (pinfunction "PWR_EN_71") (pintype "bidirectional"))
    )
    (net (code "52") (name "RTS1-PROCESSOR") (class "Default")
      (node (ref "J1") (pin "13") (pinfunction "RTS1_13") (pintype "bidirectional"))
      (node (ref "J6") (pin "18") (pinfunction "CTS_18") (pintype "bidirectional"))
    )
    (net (code "53") (name "RX1-DFU_TX-FC0-PLEX") (class "Default")
      (node (ref "J6") (pin "4") (pinfunction "MCU_DFU_TX_4") (pintype "bidirectional"))
      (node (ref "U1") (pin "P9") (pinfunction "2S1_P9") (pintype "bidirectional"))
    )
    (net (code "54") (name "RX1-PROCESSOR") (class "Default")
      (node (ref "J1") (pin "19") (pinfunction "RX1_19") (pintype "bidirectional"))
      (node (ref "U1") (pin "P6") (pinfunction "D2_P6") (pintype "bidirectional"))
    )
    (net (code "55") (name "RX1-PROCESSOR-PLEX") (class "Default")
      (node (ref "J6") (pin "13") (pinfunction "TX_13") (pintype "bidirectional"))
      (node (ref "U1") (pin "P7") (pinfunction "2S3_P7") (pintype "bidirectional"))
    )
    (net (code "56") (name "SPI_PROCESSOR_SCK") (class "Default")
      (node (ref "J1") (pin "57") (pinfunction "SPI_SCK_57") (pintype "bidirectional"))
      (node (ref "J10") (pin "5") (pinfunction "CLK/SCK_5") (pintype "bidirectional"))
      (node (ref "J6") (pin "3") (pinfunction "SPI_SCK_3") (pintype "bidirectional"))
    )
    (net (code "57") (name "SPI_PROCESSOR_SDI") (class "Default")
      (node (ref "J1") (pin "61") (pinfunction "SPI_SDI_61") (pintype "bidirectional"))
      (node (ref "J10") (pin "7") (pinfunction "DAT0/SDO_7") (pintype "bidirectional"))
      (node (ref "J6") (pin "7") (pinfunction "SPI_SDO_7") (pintype "bidirectional"))
    )
    (net (code "58") (name "SPI_PROCESSOR_SDO") (class "Default")
      (node (ref "J1") (pin "59") (pinfunction "SPI_SDO_59") (pintype "bidirectional"))
      (node (ref "J10") (pin "3") (pinfunction "CMD/SDI_3") (pintype "bidirectional"))
      (node (ref "J6") (pin "5") (pinfunction "SPI_SDI_5") (pintype "bidirectional"))
    )
    (net (code "59") (name "SWDCK") (class "Default")
      (node (ref "J1") (pin "21") (pinfunction "SWDCK_21") (pintype "bidirectional"))
      (node (ref "J5") (pin "4") (pinfunction "SWDCLK_4") (pintype "bidirectional"))
    )
    (net (code "60") (name "SWDIO") (class "Default")
      (node (ref "J1") (pin "23") (pinfunction "SWDIO_23") (pintype "bidirectional"))
      (node (ref "J5") (pin "2") (pinfunction "SWDIO_2") (pintype "bidirectional"))
      (node (ref "TP1") (pin "1") (pinfunction "1_1") (pintype "bidirectional"))
    )
    (net (code "61") (name "TX1-DFU_RX-FC0-PLEX") (class "Default")
      (node (ref "J6") (pin "6") (pinfunction "MCU_DFU_RX_6") (pintype "bidirectional"))
      (node (ref "U1") (pin "P1") (pinfunction "1S1_P1") (pintype "bidirectional"))
    )
    (net (code "62") (name "TX1-PROCESSOR") (class "Default")
      (node (ref "J1") (pin "17") (pinfunction "TX1_17") (pintype "bidirectional"))
      (node (ref "U1") (pin "P4") (pinfunction "D1_P4") (pintype "bidirectional"))
    )
    (net (code "63") (name "TX1-PROCESSOR-PLEX") (class "Default")
      (node (ref "J6") (pin "15") (pinfunction "RX_15") (pintype "bidirectional"))
      (node (ref "U1") (pin "P3") (pinfunction "1S3_P3") (pintype "bidirectional"))
    )
    (net (code "64") (name "VCC") (class "Default")
      (node (ref "5V_MEAS") (pin "1") (pinfunction "1_1") (pintype "passive"))
      (node (ref "5V_MEAS") (pin "3") (pinfunction "1_3") (pintype "passive"))
      (node (ref "C2") (pin "1") (pinfunction "1_1") (pintype "passive"))
      (node (ref "C3") (pin "1") (pinfunction "1_1") (pintype "passive"))
      (node (ref "D5") (pin "C") (pinfunction "C_C") (pintype "passive"))
      (node (ref "J6") (pin "72") (pinfunction "VCC_72") (pintype "bidirectional"))
      (node (ref "J6") (pin "74") (pinfunction "VCC_74") (pintype "bidirectional"))
      (node (ref "Q1") (pin "2") (pinfunction "S_2") (pintype "bidirectional"))
      (node (ref "R4") (pin "2") (pinfunction "2_2") (pintype "passive"))
      (node (ref "R5") (pin "1") (pinfunction "1_1") (pintype "passive"))
      (node (ref "U2") (pin "4") (pinfunction "VIN_4") (pintype "power_in"))
      (node (ref "U4") (pin "1") (pinfunction "IN_1") (pintype "input"))
    )
    (net (code "65") (name "VIN") (class "Default")
      (node (ref "BYP") (pin "2") (pinfunction "2_2") (pintype "passive"))
      (node (ref "D5") (pin "A") (pinfunction "A_A") (pintype "passive"))
      (node (ref "F2") (pin "2") (pinfunction "2_2") (pintype "bidirectional"))
      (node (ref "J1") (pin "9") (pinfunction "USB_VIN_9") (pintype "bidirectional"))
      (node (ref "Q1") (pin "1") (pinfunction "G_1") (pintype "bidirectional"))
      (node (ref "R10") (pin "2") (pinfunction "2_2") (pintype "passive"))
      (node (ref "R6") (pin "2") (pinfunction "2_2") (pintype "passive"))
      (node (ref "R8") (pin "2") (pinfunction "2_2") (pintype "passive"))
      (node (ref "TP4") (pin "1") (pinfunction "1_1") (pintype "bidirectional"))
    )
    (net (code "66") (name "VIN{slash}3") (class "Default")
      (node (ref "J1") (pin "49") (pinfunction "BATT_VIN/3_49") (pintype "bidirectional"))
      (node (ref "R10") (pin "1") (pinfunction "1_1") (pintype "passive"))
      (node (ref "R7") (pin "2") (pinfunction "2_2") (pintype "passive"))
    )
    (net (code "67") (name "V_BATT") (class "Default")
      (node (ref "C4") (pin "1") (pinfunction "1_1") (pintype "passive"))
      (node (ref "J12") (pin "2") (pinfunction "2_2") (pintype "passive"))
      (node (ref "J8") (pin "2") (pinfunction "+_2") (pintype "bidirectional"))
      (node (ref "Q1") (pin "3") (pinfunction "D_3") (pintype "bidirectional"))
      (node (ref "TP3") (pin "1") (pinfunction "1_1") (pintype "bidirectional"))
      (node (ref "U2") (pin "3") (pinfunction "VBAT_3") (pintype "power_in"))
    )
    (net (code "68") (name "V_USB") (class "Default")
      (node (ref "BYP") (pin "1") (pinfunction "1_1") (pintype "passive"))
      (node (ref "F2") (pin "1") (pinfunction "1_1") (pintype "bidirectional"))
      (node (ref "J3") (pin "VBUS1") (pinfunction "VBUS_VBUS1") (pintype "bidirectional"))
      (node (ref "J3") (pin "VBUS2") (pinfunction "VBUS_VBUS2") (pintype "bidirectional"))
      (node (ref "U3") (pin "5") (pinfunction "VCC_5") (pintype "bidirectional"))
    )
    (net (code "69") (name "unconnected-(J1-AUD_BCLK-Pad50)") (class "Default")
      (node (ref "J1") (pin "50") (pinfunction "AUD_BCLK_50") (pintype "bidirectional"))
    )
    (net (code "70") (name "unconnected-(J1-AUD_IN{slash}CAM_PCLK-Pad54)") (class "Default")
      (node (ref "J1") (pin "54") (pinfunction "AUD_IN/CAM_PCLK_54") (pintype "bidirectional"))
    )
    (net (code "71") (name "unconnected-(J1-AUD_LRCLK-Pad52)") (class "Default")
      (node (ref "J1") (pin "52") (pinfunction "AUD_LRCLK_52") (pintype "bidirectional"))
    )
    (net (code "72") (name "unconnected-(J1-AUD_MCLK-Pad58)") (class "Default")
      (node (ref "J1") (pin "58") (pinfunction "AUD_MCLK_58") (pintype "bidirectional"))
    )
    (net (code "73") (name "unconnected-(J1-AUD_OUT{slash}CAM_MCLK-Pad56)") (class "Default")
      (node (ref "J1") (pin "56") (pinfunction "AUD_OUT/CAM_MCLK_56") (pintype "bidirectional"))
    )
    (net (code "74") (name "unconnected-(J1-G5{slash}BUS5-Pad73)") (class "Default")
      (node (ref "J1") (pin "73") (pinfunction "G5/BUS5_73") (pintype "bidirectional"))
    )
    (net (code "75") (name "unconnected-(J1-G6{slash}BUS6-Pad71)") (class "Default")
      (node (ref "J1") (pin "71") (pinfunction "G6/BUS6_71") (pintype "bidirectional"))
    )
    (net (code "76") (name "unconnected-(J1-G7{slash}BUS7-Pad69)") (class "Default")
      (node (ref "J1") (pin "69") (pinfunction "G7/BUS7_69") (pintype "bidirectional"))
    )
    (net (code "77") (name "unconnected-(J1-G8-Pad67)") (class "Default")
      (node (ref "J1") (pin "67") (pinfunction "G8_67") (pintype "bidirectional"))
    )
    (net (code "78") (name "unconnected-(J1-G9{slash}ADC_D-{slash}CAM_HSYNC-Pad65)") (class "Default")
      (node (ref "J1") (pin "65") (pinfunction "G9/ADC_D-/CAM_HSYNC_65") (pintype "bidirectional"))
    )
    (net (code "79") (name "unconnected-(J1-G10{slash}ADC_D+{slash}CAM_VSYNC-Pad63)") (class "Default")
      (node (ref "J1") (pin "63") (pinfunction "G10/ADC_D+/CAM_VSYNC_63") (pintype "bidirectional"))
    )
    (net (code "80") (name "unconnected-(J1-G11-Pad8)") (class "Default")
      (node (ref "J1") (pin "8") (pinfunction "G11_8") (pintype "bidirectional"))
    )
    (net (code "81") (name "unconnected-(J1-PWM1-Pad47)") (class "Default")
      (node (ref "J1") (pin "47") (pinfunction "PWM1_47") (pintype "bidirectional"))
    )
    (net (code "82") (name "unconnected-(J1-RTC_3V-Pad72)") (class "Default")
      (node (ref "J1") (pin "72") (pinfunction "RTC_3V_72") (pintype "bidirectional"))
    )
    (net (code "83") (name "unconnected-(J1-RX2-Pad20)") (class "Default")
      (node (ref "J1") (pin "20") (pinfunction "RX2_20") (pintype "bidirectional"))
    )
    (net (code "84") (name "unconnected-(J1-SDIO_DATA1-Pad66)") (class "Default")
      (node (ref "J1") (pin "66") (pinfunction "SDIO_DATA1_66") (pintype "bidirectional"))
    )
    (net (code "85") (name "unconnected-(J1-SDIO_DATA2-Pad68)") (class "Default")
      (node (ref "J1") (pin "68") (pinfunction "SDIO_DATA2_68") (pintype "bidirectional"))
    )
    (net (code "86") (name "unconnected-(J1-SPI_SCK1{slash}SDIO_CLK-Pad60)") (class "Default")
      (node (ref "J1") (pin "60") (pinfunction "SPI_SCK1/SDIO_CLK_60") (pintype "bidirectional"))
    )
    (net (code "87") (name "unconnected-(J1-SPI_SDI1{slash}SDIO_DATA0-Pad64)") (class "Default")
      (node (ref "J1") (pin "64") (pinfunction "SPI_SDI1/SDIO_DATA0_64") (pintype "bidirectional"))
    )
    (net (code "88") (name "unconnected-(J1-SPI_SDO1{slash}SDIO_CMD-Pad62)") (class "Default")
      (node (ref "J1") (pin "62") (pinfunction "SPI_SDO1/SDIO_CMD_62") (pintype "bidirectional"))
    )
    (net (code "89") (name "unconnected-(J1-SPI_~{CS1}{slash}SDIO_DATA3-Pad70)") (class "Default")
      (node (ref "J1") (pin "70") (pinfunction "SPI_~{CS1}/SDIO_DATA3_70") (pintype "bidirectional"))
    )
    (net (code "90") (name "unconnected-(J1-TX2-Pad22)") (class "Default")
      (node (ref "J1") (pin "22") (pinfunction "TX2_22") (pintype "bidirectional"))
    )
    (net (code "91") (name "unconnected-(J5-SWO-Pad6)") (class "Default")
      (node (ref "J5") (pin "6") (pinfunction "SWO_6") (pintype "bidirectional"))
    )
    (net (code "92") (name "unconnected-(J6-EEPROM_WP-Pad40)") (class "Default")
      (node (ref "J6") (pin "40") (pinfunction "EEPROM_WP_40") (pintype "bidirectional"))
    )
    (net (code "93") (name "unconnected-(J6-USB_VIN-Pad70)") (class "Default")
      (node (ref "J6") (pin "70") (pinfunction "USB_VIN_70") (pintype "bidirectional"))
    )
    (net (code "94") (name "unconnected-(J8-PAD1-PadNC1)") (class "Default")
      (node (ref "J8") (pin "NC1") (pinfunction "PAD1_NC1") (pintype "bidirectional"))
    )
    (net (code "95") (name "unconnected-(J8-PAD2-PadNC2)") (class "Default")
      (node (ref "J8") (pin "NC2") (pinfunction "PAD2_NC2") (pintype "bidirectional"))
    )
    (net (code "96") (name "unconnected-(J10-DAT1-Pad8)") (class "Default")
      (node (ref "J10") (pin "8") (pinfunction "DAT1_8") (pintype "bidirectional"))
    )
    (net (code "97") (name "unconnected-(J10-DAT2-Pad1)") (class "Default")
      (node (ref "J10") (pin "1") (pinfunction "DAT2_1") (pintype "bidirectional"))
    )
    (net (code "98") (name "unconnected-(J10-DET-Pad9)") (class "Default")
      (node (ref "J10") (pin "9") (pinfunction "DET_9") (pintype "bidirectional"))
    )
    (net (code "99") (name "unconnected-(U1-1S2-PadP2)") (class "Default")
      (node (ref "U1") (pin "P2") (pinfunction "1S2_P2") (pintype "bidirectional"))
    )
    (net (code "100") (name "unconnected-(U1-2S2-PadP8)") (class "Default")
      (node (ref "U1") (pin "P8") (pinfunction "2S2_P8") (pintype "bidirectional"))
    )
    (net (code "101") (name "unconnected-(U3-IO1-Pad1)") (class "Default")
      (node (ref "U3") (pin "1") (pinfunction "IO1_1") (pintype "bidirectional"))
    )
    (net (code "102") (name "unconnected-(U3-IO2-Pad3)") (class "Default")
      (node (ref "U3") (pin "3") (pinfunction "IO2_3") (pintype "bidirectional"))
    )
  )
)
